# ChargeControllerMainBoard-v2.net
KiCad netlist of a schematic drawn in EAGLE
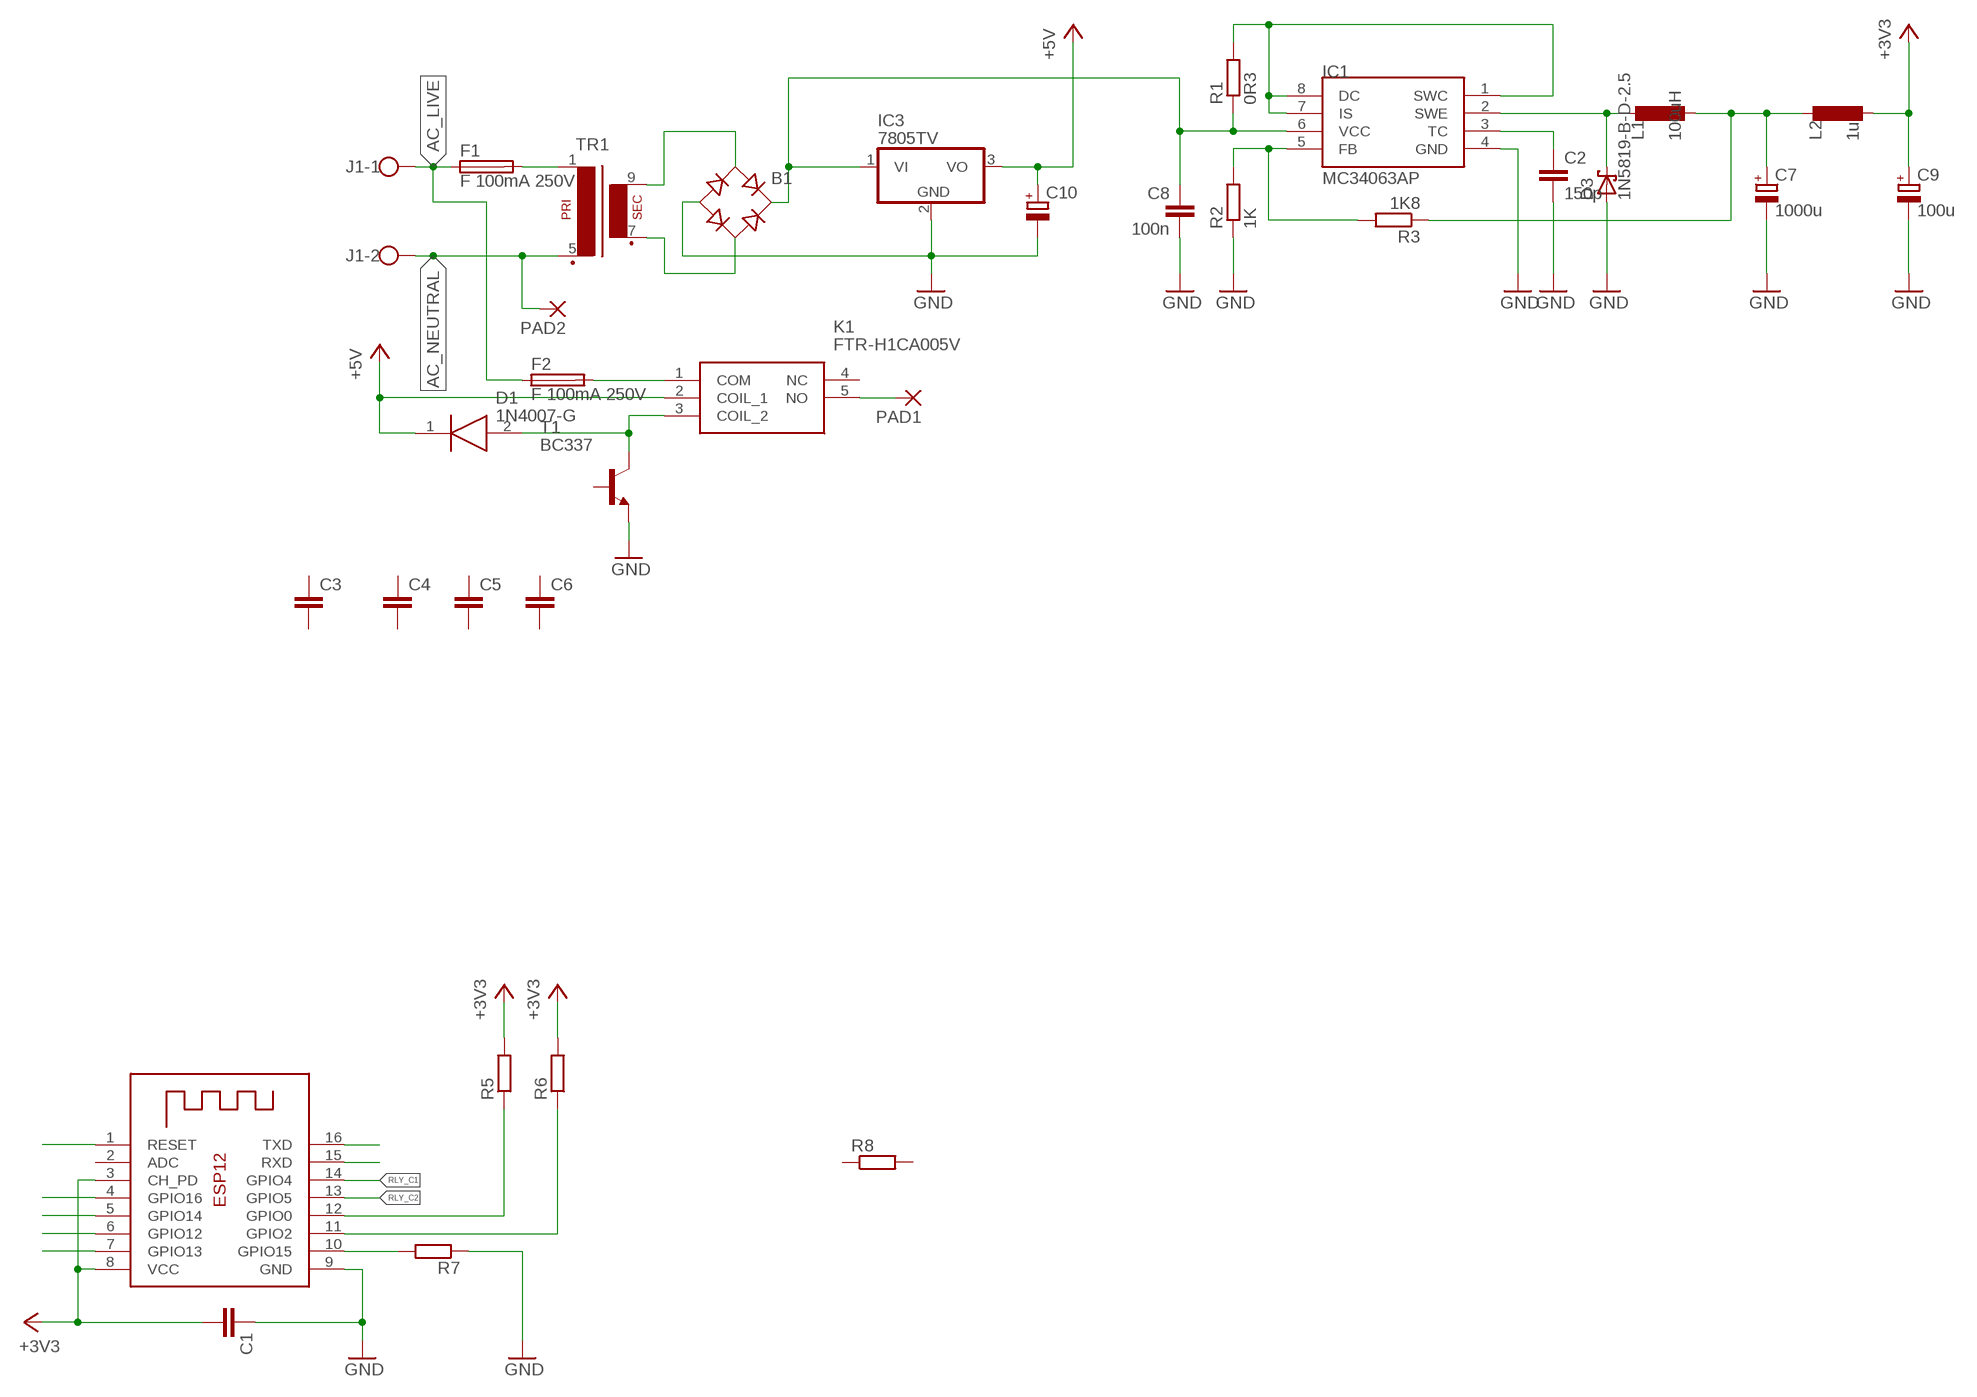
[diagram p0: schematic, sheet 1]

(export (version "E")
  (design (tool "Eeschema 10.0.6"))
  (components
    (comp (ref "B1")
      (value "B-DIL")
      (footprint "eagle-import:B-DIL")
      (libsource (lib "eagle-import") (part "B-DIL"))
    )
    (comp (ref "C1")
      (value "C-EUC0805")
      (footprint "eagle-import:C0805")
      (libsource (lib "eagle-import") (part "C-EUC0805"))
    )
    (comp (ref "C2")
      (value "150p")
      (footprint "eagle-import:C025-024X044")
      (libsource (lib "eagle-import") (part "C-EU025-024X044"))
    )
    (comp (ref "C3")
      (value "C-EUC0805")
      (footprint "eagle-import:C0805")
      (libsource (lib "eagle-import") (part "C-EUC0805"))
    )
    (comp (ref "C4")
      (value "C-EUC0805")
      (footprint "eagle-import:C0805")
      (libsource (lib "eagle-import") (part "C-EUC0805"))
    )
    (comp (ref "C5")
      (value "C-EUC0805")
      (footprint "eagle-import:C0805")
      (libsource (lib "eagle-import") (part "C-EUC0805"))
    )
    (comp (ref "C6")
      (value "C-EUC0805")
      (footprint "eagle-import:C0805")
      (libsource (lib "eagle-import") (part "C-EUC0805"))
    )
    (comp (ref "C7")
      (value "1000u")
      (footprint "eagle-import:E3,5-8")
      (libsource (lib "eagle-import") (part "CPOL-EUE3.5-8"))
    )
    (comp (ref "C8")
      (value "100n")
      (footprint "eagle-import:C025-024X044")
      (libsource (lib "eagle-import") (part "C-EU025-024X044"))
    )
    (comp (ref "C9")
      (value "100u")
      (footprint "eagle-import:E3,5-8")
      (libsource (lib "eagle-import") (part "CPOL-EUE3.5-8"))
    )
    (comp (ref "C10")
      (value "CPOL-EUE3.5-8")
      (footprint "eagle-import:E3,5-8")
      (libsource (lib "eagle-import") (part "CPOL-EUE3.5-8"))
    )
    (comp (ref "D1")
      (value "1N4007-G")
      (footprint "eagle-import:DIOAD1410W90L470D235")
      (fields (field (name "MOUSER_PART_NUMBER") "750-1N4007-G"))
      (libsource (lib "eagle-import") (part "1N4007-G"))
    )
    (comp (ref "D3")
      (value "1N5819-B-D-2.5")
      (footprint "eagle-import:D-2.5")
      (libsource (lib "eagle-import") (part "1N581-D-2.59-B"))
    )
    (comp (ref "F1")
      (value "F 100mA 250V")
      (footprint "eagle-import:SH22,5")
      (fields (field (name "MF") "SCHURTER") (field (name "MPN") "0031.8201"))
      (libsource (lib "eagle-import") (part "SH22,5"))
    )
    (comp (ref "F2")
      (value "F 100mA 250V")
      (footprint "eagle-import:SH22,5")
      (fields (field (name "MF") "SCHURTER") (field (name "MPN") "0031.8201"))
      (libsource (lib "eagle-import") (part "SH22,5"))
    )
    (comp (ref "IC1")
      (value "MC34063AP")
      (footprint "eagle-import:DIL08")
      (libsource (lib "eagle-import") (part "MC34063AP"))
    )
    (comp (ref "IC3")
      (value "7805TV")
      (footprint "eagle-import:TO220V")
      (libsource (lib "eagle-import") (part "78TV05"))
    )
    (comp (ref "J1")
      (value "W237-102")
      (footprint "eagle-import:W237-102")
      (fields (field (name "MPN") "237-102"))
      (libsource (lib "eagle-import") (part "W237-102"))
    )
    (comp (ref "K1")
      (value "FTR-H1CA005V")
      (footprint "eagle-import:FTRH1CA005V")
      (fields (field (name "MOUSER_PART_NUMBER") "817-FTR-H1CA005V"))
      (libsource (lib "eagle-import") (part "FTR-H1CA005V"))
    )
    (comp (ref "L1")
      (value "100uH")
      (footprint "eagle-import:6000-XXXX-RC")
      (libsource (lib "eagle-import") (part "L-EU6000-XXX-RC"))
    )
    (comp (ref "L2")
      (value "1u")
      (footprint "eagle-import:0204V")
      (libsource (lib "eagle-import") (part "L-EU0204V"))
    )
    (comp (ref "PAD1")
      (value "2,54/1,1")
      (footprint "eagle-import:2,54_1,1")
      (libsource (lib "eagle-import") (part "2,54/1,1"))
    )
    (comp (ref "PAD2")
      (value "2,54/1,1")
      (footprint "eagle-import:2,54_1,1")
      (libsource (lib "eagle-import") (part "2,54/1,1"))
    )
    (comp (ref "R1")
      (value "0R3")
      (footprint "eagle-import:0204V")
      (libsource (lib "eagle-import") (part "R-EU_0204/2V"))
    )
    (comp (ref "R2")
      (value "1K")
      (footprint "eagle-import:0204V")
      (libsource (lib "eagle-import") (part "R-EU_0204/2V"))
    )
    (comp (ref "R3")
      (value "1K8")
      (footprint "eagle-import:0204V")
      (libsource (lib "eagle-import") (part "R-EU_0204/2V"))
    )
    (comp (ref "R5")
      (value "R-EU_R0805")
      (footprint "eagle-import:R0805")
      (libsource (lib "eagle-import") (part "R-EU_R0805"))
    )
    (comp (ref "R6")
      (value "R-EU_R0805")
      (footprint "eagle-import:R0805")
      (libsource (lib "eagle-import") (part "R-EU_R0805"))
    )
    (comp (ref "R7")
      (value "R-EU_R0805")
      (footprint "eagle-import:R0805")
      (libsource (lib "eagle-import") (part "R-EU_R0805"))
    )
    (comp (ref "R8")
      (value "R-EU_R0805")
      (footprint "eagle-import:R0805")
      (libsource (lib "eagle-import") (part "R-EU_R0805"))
    )
    (comp (ref "T1")
      (value "BC337")
      (footprint "eagle-import:TO92")
      (libsource (lib "eagle-import") (part "BC337"))
    )
    (comp (ref "TR1")
      (value "EI30-1")
      (footprint "eagle-import:EI30-1")
      (libsource (lib "eagle-import") (part "EI30-1"))
    )
    (comp (ref "X1")
      (value "ESP-12")
      (footprint "eagle-import:ESP-12")
      (libsource (lib "eagle-import") (part "ESP-12"))
    )
  )
  (nets
    (net (code "1") (name "+3V3") (class "Default")
      (node (ref "C1") (pin "2") (pinfunction "2_2") (pintype "passive"))
      (node (ref "C9") (pin "+") (pinfunction "+_+") (pintype "passive"))
      (node (ref "L2") (pin "2") (pinfunction "2_2") (pintype "passive"))
      (node (ref "R5") (pin "2") (pinfunction "2_2") (pintype "passive"))
      (node (ref "R6") (pin "2") (pinfunction "2_2") (pintype "passive"))
      (node (ref "X1") (pin "3") (pinfunction "CH_PD_3") (pintype "input"))
      (node (ref "X1") (pin "8") (pinfunction "VCC_8") (pintype "power_in"))
    )
    (net (code "2") (name "+5V") (class "Default")
      (node (ref "C10") (pin "+") (pinfunction "+_+") (pintype "passive"))
      (node (ref "D1") (pin "1") (pinfunction "K_1") (pintype "bidirectional"))
      (node (ref "IC3") (pin "3") (pinfunction "VO_3") (pintype "passive"))
      (node (ref "K1") (pin "2") (pinfunction "COIL_1_2") (pintype "bidirectional"))
    )
    (net (code "3") (name "AC_LIVE") (class "Default")
      (node (ref "F1") (pin "1") (pinfunction "1_1") (pintype "passive"))
      (node (ref "F2") (pin "1") (pinfunction "1_1") (pintype "passive"))
      (node (ref "J1") (pin "1") (pinfunction "KL_1") (pintype "passive"))
    )
    (net (code "4") (name "AC_NEUTRAL") (class "Default")
      (node (ref "J1") (pin "2") (pinfunction "KL_2") (pintype "passive"))
      (node (ref "PAD2") (pin "1") (pinfunction "P_1") (pintype "passive"))
      (node (ref "TR1") (pin "5") (pinfunction "P2_5") (pintype "passive"))
    )
    (net (code "5") (name "GND") (class "Default")
      (node (ref "B1") (pin "-") (pinfunction "-_-") (pintype "passive"))
      (node (ref "C1") (pin "1") (pinfunction "1_1") (pintype "passive"))
      (node (ref "C10") (pin "-") (pinfunction "-_-") (pintype "passive"))
      (node (ref "C2") (pin "2") (pinfunction "2_2") (pintype "passive"))
      (node (ref "C7") (pin "-") (pinfunction "-_-") (pintype "passive"))
      (node (ref "C8") (pin "2") (pinfunction "2_2") (pintype "passive"))
      (node (ref "C9") (pin "-") (pinfunction "-_-") (pintype "passive"))
      (node (ref "D3") (pin "A") (pinfunction "A_A") (pintype "passive"))
      (node (ref "IC1") (pin "4") (pinfunction "GND_4") (pintype "passive"))
      (node (ref "IC3") (pin "2") (pinfunction "GND_2") (pintype "passive"))
      (node (ref "R2") (pin "1") (pinfunction "1_1") (pintype "passive"))
      (node (ref "R7") (pin "1") (pinfunction "1_1") (pintype "passive"))
      (node (ref "T1") (pin "1") (pinfunction "E_1") (pintype "passive"))
      (node (ref "X1") (pin "9") (pinfunction "GND_9") (pintype "power_in"))
    )
    (net (code "6") (name "Net-(C7-Pad+)") (class "Default")
      (node (ref "C7") (pin "+") (pinfunction "+_+") (pintype "passive"))
      (node (ref "L1") (pin "2") (pinfunction "2_2") (pintype "passive"))
      (node (ref "L2") (pin "1") (pinfunction "1_1") (pintype "passive"))
      (node (ref "R3") (pin "1") (pinfunction "1_1") (pintype "passive"))
    )
    (net (code "7") (name "Net-(D1-A)") (class "Default")
      (node (ref "D1") (pin "2") (pinfunction "A_2") (pintype "bidirectional"))
      (node (ref "K1") (pin "3") (pinfunction "COIL_2_3") (pintype "bidirectional"))
      (node (ref "T1") (pin "3") (pinfunction "C_3") (pintype "passive"))
    )
    (net (code "8") (name "Net-(IC1-DC)") (class "Default")
      (node (ref "IC1") (pin "1") (pinfunction "SWC_1") (pintype "passive"))
      (node (ref "IC1") (pin "7") (pinfunction "IS_7") (pintype "passive"))
      (node (ref "IC1") (pin "8") (pinfunction "DC_8") (pintype "passive"))
      (node (ref "R1") (pin "2") (pinfunction "2_2") (pintype "passive"))
    )
    (net (code "9") (name "Net-(IC1-FB)") (class "Default")
      (node (ref "IC1") (pin "5") (pinfunction "FB_5") (pintype "passive"))
      (node (ref "R2") (pin "2") (pinfunction "2_2") (pintype "passive"))
      (node (ref "R3") (pin "2") (pinfunction "2_2") (pintype "passive"))
    )
    (net (code "10") (name "Net-(IC1-SWE)") (class "Default")
      (node (ref "D3") (pin "C") (pinfunction "C_C") (pintype "passive"))
      (node (ref "IC1") (pin "2") (pinfunction "SWE_2") (pintype "passive"))
      (node (ref "L1") (pin "1") (pinfunction "1_1") (pintype "passive"))
    )
    (net (code "11") (name "Net-(IC1-TC)") (class "Default")
      (node (ref "C2") (pin "1") (pinfunction "1_1") (pintype "passive"))
      (node (ref "IC1") (pin "3") (pinfunction "TC_3") (pintype "passive"))
    )
    (net (code "12") (name "Net-(IC1-VCC)") (class "Default")
      (node (ref "B1") (pin "+") (pinfunction "+_+") (pintype "passive"))
      (node (ref "C8") (pin "1") (pinfunction "1_1") (pintype "passive"))
      (node (ref "IC1") (pin "6") (pinfunction "VCC_6") (pintype "passive"))
      (node (ref "IC3") (pin "1") (pinfunction "VI_1") (pintype "input"))
      (node (ref "R1") (pin "1") (pinfunction "1_1") (pintype "passive"))
    )
    (net (code "13") (name "Net-(K1-COM)") (class "Default")
      (node (ref "F2") (pin "2") (pinfunction "2_2") (pintype "passive"))
      (node (ref "K1") (pin "1") (pinfunction "COM_1") (pintype "bidirectional"))
    )
    (net (code "14") (name "Net-(K1-NO)") (class "Default")
      (node (ref "K1") (pin "5") (pinfunction "NO_5") (pintype "bidirectional"))
      (node (ref "PAD1") (pin "1") (pinfunction "P_1") (pintype "passive"))
    )
    (net (code "15") (name "Net-(TR1-P1)") (class "Default")
      (node (ref "F1") (pin "2") (pinfunction "2_2") (pintype "passive"))
      (node (ref "TR1") (pin "1") (pinfunction "P1_1") (pintype "passive"))
    )
    (net (code "16") (name "Net-(TR1-S3)") (class "Default")
      (node (ref "B1") (pin "AC2") (pinfunction "AC2_AC2") (pintype "passive"))
      (node (ref "TR1") (pin "7") (pinfunction "S3_7") (pintype "passive"))
    )
    (net (code "17") (name "Net-(TR1-S4)") (class "Default")
      (node (ref "B1") (pin "AC1") (pinfunction "AC1_AC1") (pintype "passive"))
      (node (ref "TR1") (pin "9") (pinfunction "S4_9") (pintype "passive"))
    )
    (net (code "18") (name "Net-(X1-GPIO0)") (class "Default")
      (node (ref "R5") (pin "1") (pinfunction "1_1") (pintype "passive"))
      (node (ref "X1") (pin "12") (pinfunction "GPIO0_12") (pintype "bidirectional"))
    )
    (net (code "19") (name "Net-(X1-GPIO2)") (class "Default")
      (node (ref "R6") (pin "1") (pinfunction "1_1") (pintype "passive"))
      (node (ref "X1") (pin "11") (pinfunction "GPIO2_11") (pintype "bidirectional"))
    )
    (net (code "20") (name "Net-(X1-GPIO15)") (class "Default")
      (node (ref "R7") (pin "2") (pinfunction "2_2") (pintype "passive"))
      (node (ref "X1") (pin "10") (pinfunction "GPIO15_10") (pintype "bidirectional"))
    )
    (net (code "21") (name "RLY_C1") (class "Default")
      (node (ref "X1") (pin "14") (pinfunction "GPIO4_14") (pintype "bidirectional"))
    )
    (net (code "22") (name "RLY_C2") (class "Default")
      (node (ref "X1") (pin "13") (pinfunction "GPIO5_13") (pintype "bidirectional"))
    )
    (net (code "23") (name "unconnected-(C3-Pad1)") (class "Default")
      (node (ref "C3") (pin "1") (pinfunction "1_1") (pintype "passive"))
    )
    (net (code "24") (name "unconnected-(C3-Pad2)") (class "Default")
      (node (ref "C3") (pin "2") (pinfunction "2_2") (pintype "passive"))
    )
    (net (code "25") (name "unconnected-(C4-Pad1)") (class "Default")
      (node (ref "C4") (pin "1") (pinfunction "1_1") (pintype "passive"))
    )
    (net (code "26") (name "unconnected-(C4-Pad2)") (class "Default")
      (node (ref "C4") (pin "2") (pinfunction "2_2") (pintype "passive"))
    )
    (net (code "27") (name "unconnected-(C5-Pad1)") (class "Default")
      (node (ref "C5") (pin "1") (pinfunction "1_1") (pintype "passive"))
    )
    (net (code "28") (name "unconnected-(C5-Pad2)") (class "Default")
      (node (ref "C5") (pin "2") (pinfunction "2_2") (pintype "passive"))
    )
    (net (code "29") (name "unconnected-(C6-Pad1)") (class "Default")
      (node (ref "C6") (pin "1") (pinfunction "1_1") (pintype "passive"))
    )
    (net (code "30") (name "unconnected-(C6-Pad2)") (class "Default")
      (node (ref "C6") (pin "2") (pinfunction "2_2") (pintype "passive"))
    )
    (net (code "31") (name "unconnected-(K1-NC-Pad4)") (class "Default")
      (node (ref "K1") (pin "4") (pinfunction "NC_4") (pintype "no_connect"))
    )
    (net (code "32") (name "unconnected-(R8-Pad1)") (class "Default")
      (node (ref "R8") (pin "1") (pinfunction "1_1") (pintype "passive"))
    )
    (net (code "33") (name "unconnected-(R8-Pad2)") (class "Default")
      (node (ref "R8") (pin "2") (pinfunction "2_2") (pintype "passive"))
    )
    (net (code "34") (name "unconnected-(T1-B-Pad2)") (class "Default")
      (node (ref "T1") (pin "2") (pinfunction "B_2") (pintype "passive"))
    )
    (net (code "35") (name "unconnected-(X1-ADC-Pad2)") (class "Default")
      (node (ref "X1") (pin "2") (pinfunction "ADC_2") (pintype "passive"))
    )
    (net (code "36") (name "unconnected-(X1-GPIO12-Pad6)") (class "Default")
      (node (ref "X1") (pin "6") (pinfunction "GPIO12_6") (pintype "bidirectional"))
    )
    (net (code "37") (name "unconnected-(X1-GPIO13-Pad7)") (class "Default")
      (node (ref "X1") (pin "7") (pinfunction "GPIO13_7") (pintype "bidirectional"))
    )
    (net (code "38") (name "unconnected-(X1-GPIO14-Pad5)") (class "Default")
      (node (ref "X1") (pin "5") (pinfunction "GPIO14_5") (pintype "bidirectional"))
    )
    (net (code "39") (name "unconnected-(X1-GPIO16-Pad4)") (class "Default")
      (node (ref "X1") (pin "4") (pinfunction "GPIO16_4") (pintype "bidirectional"))
    )
    (net (code "40") (name "unconnected-(X1-RESET-Pad1)") (class "Default")
      (node (ref "X1") (pin "1") (pinfunction "RESET_1") (pintype "input"))
    )
    (net (code "41") (name "unconnected-(X1-RXD-Pad15)") (class "Default")
      (node (ref "X1") (pin "15") (pinfunction "RXD_15") (pintype "input"))
    )
    (net (code "42") (name "unconnected-(X1-TXD-Pad16)") (class "Default")
      (node (ref "X1") (pin "16") (pinfunction "TXD_16") (pintype "output"))
    )
  )
)
